# MODULO2_2.net
KiCad netlist of a schematic drawn in EAGLE
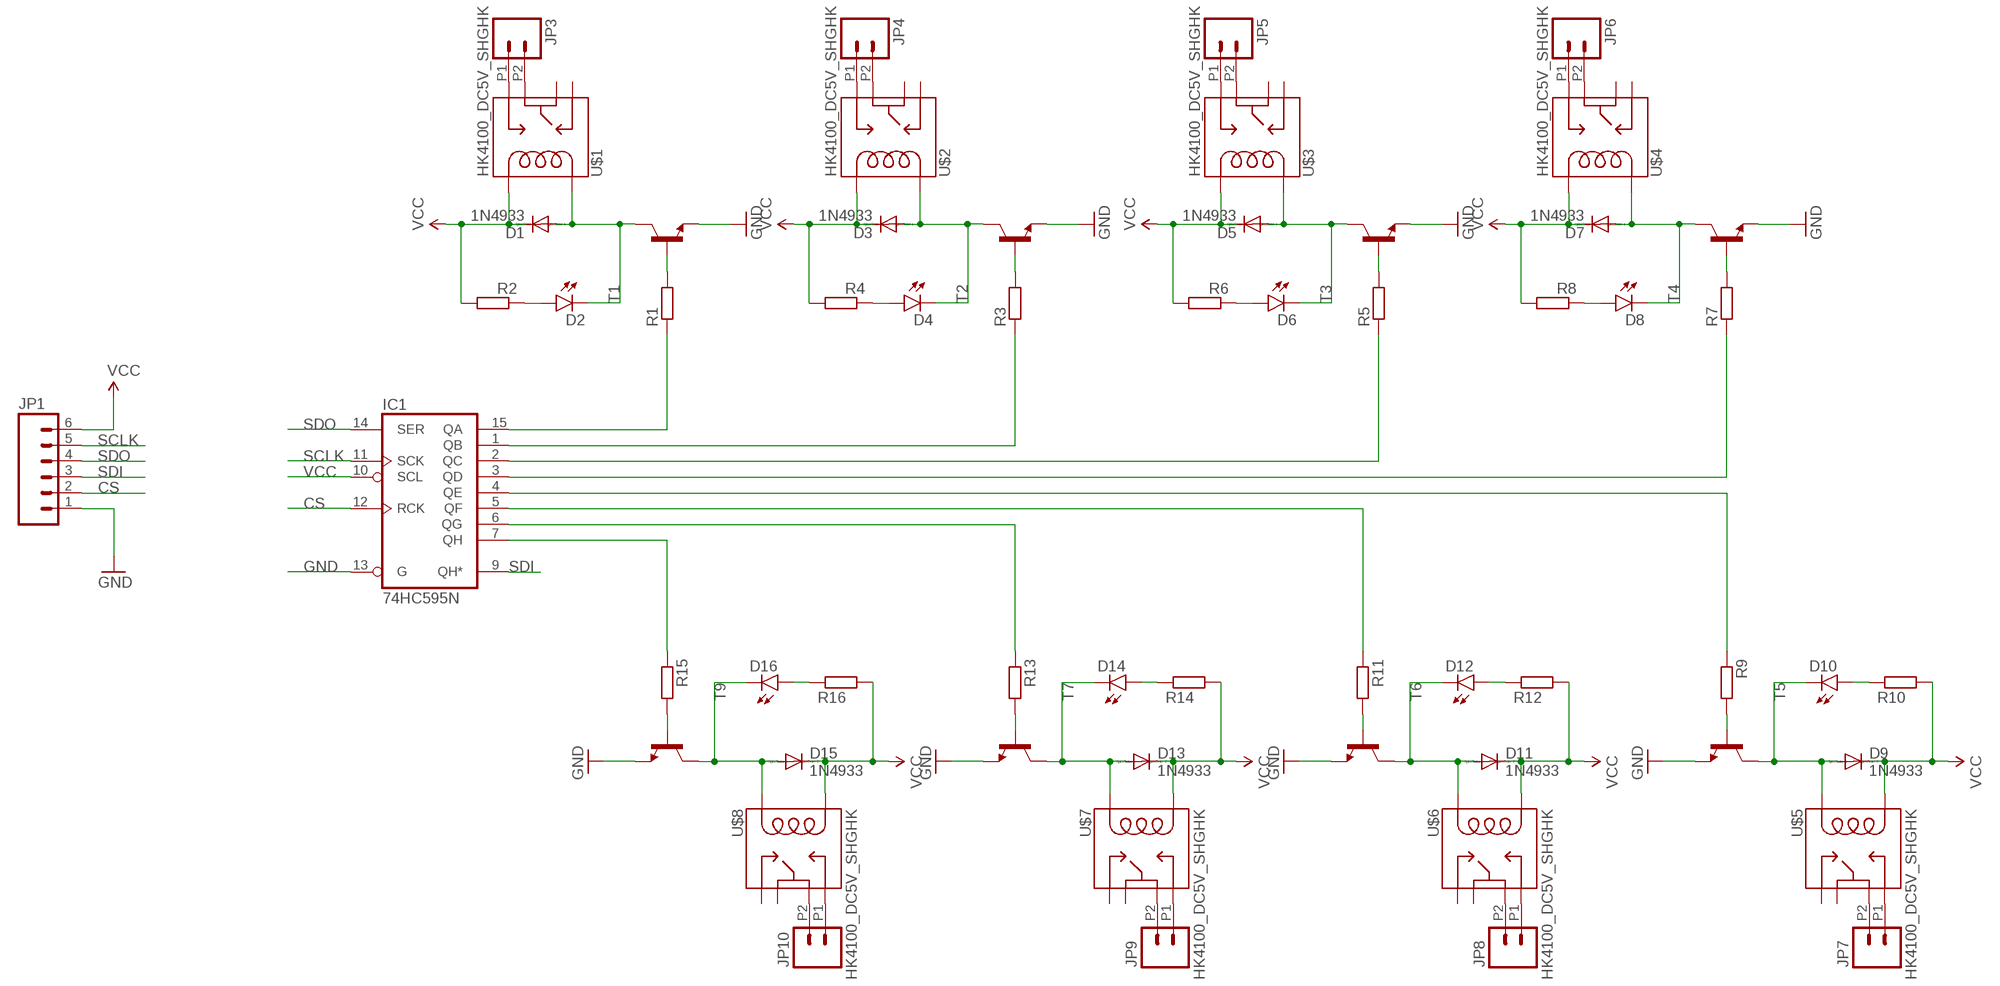
[diagram p0: schematic, sheet 1]

(export (version "E")
  (design (tool "Eeschema 10.0.6"))
  (components
    (comp (ref "D1")
      (value "1N4933")
      (footprint "eagle-import:DO41-10")
      (libsource (lib "eagle-import") (part "1N4933"))
    )
    (comp (ref "D2")
      (value "LED5MM")
      (footprint "eagle-import:LED5MM")
      (libsource (lib "eagle-import") (part "LED5MM"))
    )
    (comp (ref "D3")
      (value "1N4933")
      (footprint "eagle-import:DO41-10")
      (libsource (lib "eagle-import") (part "1N4933"))
    )
    (comp (ref "D4")
      (value "LED5MM")
      (footprint "eagle-import:LED5MM")
      (libsource (lib "eagle-import") (part "LED5MM"))
    )
    (comp (ref "D5")
      (value "1N4933")
      (footprint "eagle-import:DO41-10")
      (libsource (lib "eagle-import") (part "1N4933"))
    )
    (comp (ref "D6")
      (value "LED5MM")
      (footprint "eagle-import:LED5MM")
      (libsource (lib "eagle-import") (part "LED5MM"))
    )
    (comp (ref "D7")
      (value "1N4933")
      (footprint "eagle-import:DO41-10")
      (libsource (lib "eagle-import") (part "1N4933"))
    )
    (comp (ref "D8")
      (value "LED5MM")
      (footprint "eagle-import:LED5MM")
      (libsource (lib "eagle-import") (part "LED5MM"))
    )
    (comp (ref "D9")
      (value "1N4933")
      (footprint "eagle-import:DO41-10")
      (libsource (lib "eagle-import") (part "1N4933"))
    )
    (comp (ref "D10")
      (value "LED5MM")
      (footprint "eagle-import:LED5MM")
      (libsource (lib "eagle-import") (part "LED5MM"))
    )
    (comp (ref "D11")
      (value "1N4933")
      (footprint "eagle-import:DO41-10")
      (libsource (lib "eagle-import") (part "1N4933"))
    )
    (comp (ref "D12")
      (value "LED5MM")
      (footprint "eagle-import:LED5MM")
      (libsource (lib "eagle-import") (part "LED5MM"))
    )
    (comp (ref "D13")
      (value "1N4933")
      (footprint "eagle-import:DO41-10")
      (libsource (lib "eagle-import") (part "1N4933"))
    )
    (comp (ref "D14")
      (value "LED5MM")
      (footprint "eagle-import:LED5MM")
      (libsource (lib "eagle-import") (part "LED5MM"))
    )
    (comp (ref "D15")
      (value "1N4933")
      (footprint "eagle-import:DO41-10")
      (libsource (lib "eagle-import") (part "1N4933"))
    )
    (comp (ref "D16")
      (value "LED5MM")
      (footprint "eagle-import:LED5MM")
      (libsource (lib "eagle-import") (part "LED5MM"))
    )
    (comp (ref "IC1")
      (value "74HC595N")
      (footprint "eagle-import:DIL16")
      (libsource (lib "eagle-import") (part "74595NHC"))
    )
    (comp (ref "JP1")
      (value "M06LOCK")
      (footprint "eagle-import:1X06_LOCK")
      (libsource (lib "eagle-import") (part "M06LOCK"))
    )
    (comp (ref "JP3")
      (value "M022.54MM_SCREWTERM")
      (footprint "eagle-import:1X02_2.54_SCREWTERM")
      (libsource (lib "eagle-import") (part "M022.54MM_SCREWTERM"))
    )
    (comp (ref "JP4")
      (value "M022.54MM_SCREWTERM")
      (footprint "eagle-import:1X02_2.54_SCREWTERM")
      (libsource (lib "eagle-import") (part "M022.54MM_SCREWTERM"))
    )
    (comp (ref "JP5")
      (value "M022.54MM_SCREWTERM")
      (footprint "eagle-import:1X02_2.54_SCREWTERM")
      (libsource (lib "eagle-import") (part "M022.54MM_SCREWTERM"))
    )
    (comp (ref "JP6")
      (value "M022.54MM_SCREWTERM")
      (footprint "eagle-import:1X02_2.54_SCREWTERM")
      (libsource (lib "eagle-import") (part "M022.54MM_SCREWTERM"))
    )
    (comp (ref "JP7")
      (value "M022.54MM_SCREWTERM")
      (footprint "eagle-import:1X02_2.54_SCREWTERM")
      (libsource (lib "eagle-import") (part "M022.54MM_SCREWTERM"))
    )
    (comp (ref "JP8")
      (value "M022.54MM_SCREWTERM")
      (footprint "eagle-import:1X02_2.54_SCREWTERM")
      (libsource (lib "eagle-import") (part "M022.54MM_SCREWTERM"))
    )
    (comp (ref "JP9")
      (value "M022.54MM_SCREWTERM")
      (footprint "eagle-import:1X02_2.54_SCREWTERM")
      (libsource (lib "eagle-import") (part "M022.54MM_SCREWTERM"))
    )
    (comp (ref "JP10")
      (value "M022.54MM_SCREWTERM")
      (footprint "eagle-import:1X02_2.54_SCREWTERM")
      (libsource (lib "eagle-import") (part "M022.54MM_SCREWTERM"))
    )
    (comp (ref "R1")
      (value "R-EU_R0805")
      (footprint "eagle-import:R0805")
      (libsource (lib "eagle-import") (part "R-EU_R0805"))
    )
    (comp (ref "R2")
      (value "R-EU_R0805")
      (footprint "eagle-import:R0805")
      (libsource (lib "eagle-import") (part "R-EU_R0805"))
    )
    (comp (ref "R3")
      (value "R-EU_R0805")
      (footprint "eagle-import:R0805")
      (libsource (lib "eagle-import") (part "R-EU_R0805"))
    )
    (comp (ref "R4")
      (value "R-EU_R0805")
      (footprint "eagle-import:R0805")
      (libsource (lib "eagle-import") (part "R-EU_R0805"))
    )
    (comp (ref "R5")
      (value "R-EU_R0805")
      (footprint "eagle-import:R0805")
      (libsource (lib "eagle-import") (part "R-EU_R0805"))
    )
    (comp (ref "R6")
      (value "R-EU_R0805")
      (footprint "eagle-import:R0805")
      (libsource (lib "eagle-import") (part "R-EU_R0805"))
    )
    (comp (ref "R7")
      (value "R-EU_R0805")
      (footprint "eagle-import:R0805")
      (libsource (lib "eagle-import") (part "R-EU_R0805"))
    )
    (comp (ref "R8")
      (value "R-EU_R0805")
      (footprint "eagle-import:R0805")
      (libsource (lib "eagle-import") (part "R-EU_R0805"))
    )
    (comp (ref "R9")
      (value "R-EU_R0805")
      (footprint "eagle-import:R0805")
      (libsource (lib "eagle-import") (part "R-EU_R0805"))
    )
    (comp (ref "R10")
      (value "R-EU_R0805")
      (footprint "eagle-import:R0805")
      (libsource (lib "eagle-import") (part "R-EU_R0805"))
    )
    (comp (ref "R11")
      (value "R-EU_R0805")
      (footprint "eagle-import:R0805")
      (libsource (lib "eagle-import") (part "R-EU_R0805"))
    )
    (comp (ref "R12")
      (value "R-EU_R0805")
      (footprint "eagle-import:R0805")
      (libsource (lib "eagle-import") (part "R-EU_R0805"))
    )
    (comp (ref "R13")
      (value "R-EU_R0805")
      (footprint "eagle-import:R0805")
      (libsource (lib "eagle-import") (part "R-EU_R0805"))
    )
    (comp (ref "R14")
      (value "R-EU_R0805")
      (footprint "eagle-import:R0805")
      (libsource (lib "eagle-import") (part "R-EU_R0805"))
    )
    (comp (ref "R15")
      (value "R-EU_R0805")
      (footprint "eagle-import:R0805")
      (libsource (lib "eagle-import") (part "R-EU_R0805"))
    )
    (comp (ref "R16")
      (value "R-EU_R0805")
      (footprint "eagle-import:R0805")
      (libsource (lib "eagle-import") (part "R-EU_R0805"))
    )
    (comp (ref "T1")
      (value "-NPN-TO92-EBC")
      (footprint "eagle-import:TO92-EBC")
      (libsource (lib "eagle-import") (part "-NPN-TO92-EBC"))
    )
    (comp (ref "T2")
      (value "-NPN-TO92-EBC")
      (footprint "eagle-import:TO92-EBC")
      (libsource (lib "eagle-import") (part "-NPN-TO92-EBC"))
    )
    (comp (ref "T3")
      (value "-NPN-TO92-EBC")
      (footprint "eagle-import:TO92-EBC")
      (libsource (lib "eagle-import") (part "-NPN-TO92-EBC"))
    )
    (comp (ref "T4")
      (value "-NPN-TO92-EBC")
      (footprint "eagle-import:TO92-EBC")
      (libsource (lib "eagle-import") (part "-NPN-TO92-EBC"))
    )
    (comp (ref "T5")
      (value "-NPN-TO92-EBC")
      (footprint "eagle-import:TO92-EBC")
      (libsource (lib "eagle-import") (part "-NPN-TO92-EBC"))
    )
    (comp (ref "T6")
      (value "-NPN-TO92-EBC")
      (footprint "eagle-import:TO92-EBC")
      (libsource (lib "eagle-import") (part "-NPN-TO92-EBC"))
    )
    (comp (ref "T7")
      (value "-NPN-TO92-EBC")
      (footprint "eagle-import:TO92-EBC")
      (libsource (lib "eagle-import") (part "-NPN-TO92-EBC"))
    )
    (comp (ref "T9")
      (value "-NPN-TO92-EBC")
      (footprint "eagle-import:TO92-EBC")
      (libsource (lib "eagle-import") (part "-NPN-TO92-EBC"))
    )
    (comp (ref "U$1")
      (value "HK4100_DC5V_SHGHK")
      (footprint "eagle-import:HK4100")
      (libsource (lib "eagle-import") (part "HK4100_DC5V_SHGHK"))
    )
    (comp (ref "U$2")
      (value "HK4100_DC5V_SHGHK")
      (footprint "eagle-import:HK4100")
      (libsource (lib "eagle-import") (part "HK4100_DC5V_SHGHK"))
    )
    (comp (ref "U$3")
      (value "HK4100_DC5V_SHGHK")
      (footprint "eagle-import:HK4100")
      (libsource (lib "eagle-import") (part "HK4100_DC5V_SHGHK"))
    )
    (comp (ref "U$4")
      (value "HK4100_DC5V_SHGHK")
      (footprint "eagle-import:HK4100")
      (libsource (lib "eagle-import") (part "HK4100_DC5V_SHGHK"))
    )
    (comp (ref "U$5")
      (value "HK4100_DC5V_SHGHK")
      (footprint "eagle-import:HK4100")
      (libsource (lib "eagle-import") (part "HK4100_DC5V_SHGHK"))
    )
    (comp (ref "U$6")
      (value "HK4100_DC5V_SHGHK")
      (footprint "eagle-import:HK4100")
      (libsource (lib "eagle-import") (part "HK4100_DC5V_SHGHK"))
    )
    (comp (ref "U$7")
      (value "HK4100_DC5V_SHGHK")
      (footprint "eagle-import:HK4100")
      (libsource (lib "eagle-import") (part "HK4100_DC5V_SHGHK"))
    )
    (comp (ref "U$8")
      (value "HK4100_DC5V_SHGHK")
      (footprint "eagle-import:HK4100")
      (libsource (lib "eagle-import") (part "HK4100_DC5V_SHGHK"))
    )
  )
  (nets
    (net (code "1") (name "/CS") (class "Default")
      (node (ref "IC1") (pin "12") (pinfunction "RCK_12") (pintype "input"))
      (node (ref "JP1") (pin "2") (pinfunction "2_2") (pintype "passive"))
    )
    (net (code "2") (name "/SCLK") (class "Default")
      (node (ref "IC1") (pin "11") (pinfunction "SCK_11") (pintype "input"))
      (node (ref "JP1") (pin "5") (pinfunction "5_5") (pintype "passive"))
    )
    (net (code "3") (name "/SDI") (class "Default")
      (node (ref "IC1") (pin "9") (pinfunction "QH*_9") (pintype "tri_state"))
      (node (ref "JP1") (pin "3") (pinfunction "3_3") (pintype "passive"))
    )
    (net (code "4") (name "/SDO") (class "Default")
      (node (ref "IC1") (pin "14") (pinfunction "SER_14") (pintype "input"))
      (node (ref "JP1") (pin "4") (pinfunction "4_4") (pintype "passive"))
    )
    (net (code "5") (name "GND") (class "Default")
      (node (ref "IC1") (pin "13") (pinfunction "G_13") (pintype "input"))
      (node (ref "JP1") (pin "1") (pinfunction "1_1") (pintype "passive"))
      (node (ref "T1") (pin "E") (pinfunction "E_E") (pintype "passive"))
      (node (ref "T2") (pin "E") (pinfunction "E_E") (pintype "passive"))
      (node (ref "T3") (pin "E") (pinfunction "E_E") (pintype "passive"))
      (node (ref "T4") (pin "E") (pinfunction "E_E") (pintype "passive"))
      (node (ref "T5") (pin "E") (pinfunction "E_E") (pintype "passive"))
      (node (ref "T6") (pin "E") (pinfunction "E_E") (pintype "passive"))
      (node (ref "T7") (pin "E") (pinfunction "E_E") (pintype "passive"))
      (node (ref "T9") (pin "E") (pinfunction "E_E") (pintype "passive"))
    )
    (net (code "6") (name "Net-(D2-C)") (class "Default")
      (node (ref "D1") (pin "A") (pinfunction "A_A") (pintype "passive"))
      (node (ref "D2") (pin "K") (pinfunction "C_K") (pintype "passive"))
      (node (ref "T1") (pin "C") (pinfunction "C_C") (pintype "passive"))
      (node (ref "U$1") (pin "6") (pinfunction "2_6") (pintype "bidirectional"))
    )
    (net (code "7") (name "Net-(D2-PadA)") (class "Default")
      (node (ref "D2") (pin "A") (pinfunction "A_A") (pintype "passive"))
      (node (ref "R2") (pin "1") (pinfunction "1_1") (pintype "passive"))
    )
    (net (code "8") (name "Net-(D4-C)") (class "Default")
      (node (ref "D3") (pin "A") (pinfunction "A_A") (pintype "passive"))
      (node (ref "D4") (pin "K") (pinfunction "C_K") (pintype "passive"))
      (node (ref "T2") (pin "C") (pinfunction "C_C") (pintype "passive"))
      (node (ref "U$2") (pin "6") (pinfunction "2_6") (pintype "bidirectional"))
    )
    (net (code "9") (name "Net-(D4-PadA)") (class "Default")
      (node (ref "D4") (pin "A") (pinfunction "A_A") (pintype "passive"))
      (node (ref "R4") (pin "1") (pinfunction "1_1") (pintype "passive"))
    )
    (net (code "10") (name "Net-(D6-C)") (class "Default")
      (node (ref "D5") (pin "A") (pinfunction "A_A") (pintype "passive"))
      (node (ref "D6") (pin "K") (pinfunction "C_K") (pintype "passive"))
      (node (ref "T3") (pin "C") (pinfunction "C_C") (pintype "passive"))
      (node (ref "U$3") (pin "6") (pinfunction "2_6") (pintype "bidirectional"))
    )
    (net (code "11") (name "Net-(D6-PadA)") (class "Default")
      (node (ref "D6") (pin "A") (pinfunction "A_A") (pintype "passive"))
      (node (ref "R6") (pin "1") (pinfunction "1_1") (pintype "passive"))
    )
    (net (code "12") (name "Net-(D8-C)") (class "Default")
      (node (ref "D7") (pin "A") (pinfunction "A_A") (pintype "passive"))
      (node (ref "D8") (pin "K") (pinfunction "C_K") (pintype "passive"))
      (node (ref "T4") (pin "C") (pinfunction "C_C") (pintype "passive"))
      (node (ref "U$4") (pin "6") (pinfunction "2_6") (pintype "bidirectional"))
    )
    (net (code "13") (name "Net-(D8-PadA)") (class "Default")
      (node (ref "D8") (pin "A") (pinfunction "A_A") (pintype "passive"))
      (node (ref "R8") (pin "1") (pinfunction "1_1") (pintype "passive"))
    )
    (net (code "14") (name "Net-(D10-C)") (class "Default")
      (node (ref "D10") (pin "K") (pinfunction "C_K") (pintype "passive"))
      (node (ref "D9") (pin "A") (pinfunction "A_A") (pintype "passive"))
      (node (ref "T5") (pin "C") (pinfunction "C_C") (pintype "passive"))
      (node (ref "U$5") (pin "6") (pinfunction "2_6") (pintype "bidirectional"))
    )
    (net (code "15") (name "Net-(D10-PadA)") (class "Default")
      (node (ref "D10") (pin "A") (pinfunction "A_A") (pintype "passive"))
      (node (ref "R10") (pin "1") (pinfunction "1_1") (pintype "passive"))
    )
    (net (code "16") (name "Net-(D12-C)") (class "Default")
      (node (ref "D11") (pin "A") (pinfunction "A_A") (pintype "passive"))
      (node (ref "D12") (pin "K") (pinfunction "C_K") (pintype "passive"))
      (node (ref "T6") (pin "C") (pinfunction "C_C") (pintype "passive"))
      (node (ref "U$6") (pin "6") (pinfunction "2_6") (pintype "bidirectional"))
    )
    (net (code "17") (name "Net-(D12-PadA)") (class "Default")
      (node (ref "D12") (pin "A") (pinfunction "A_A") (pintype "passive"))
      (node (ref "R12") (pin "1") (pinfunction "1_1") (pintype "passive"))
    )
    (net (code "18") (name "Net-(D14-C)") (class "Default")
      (node (ref "D13") (pin "A") (pinfunction "A_A") (pintype "passive"))
      (node (ref "D14") (pin "K") (pinfunction "C_K") (pintype "passive"))
      (node (ref "T7") (pin "C") (pinfunction "C_C") (pintype "passive"))
      (node (ref "U$7") (pin "6") (pinfunction "2_6") (pintype "bidirectional"))
    )
    (net (code "19") (name "Net-(D14-PadA)") (class "Default")
      (node (ref "D14") (pin "A") (pinfunction "A_A") (pintype "passive"))
      (node (ref "R14") (pin "1") (pinfunction "1_1") (pintype "passive"))
    )
    (net (code "20") (name "Net-(D16-C)") (class "Default")
      (node (ref "D15") (pin "A") (pinfunction "A_A") (pintype "passive"))
      (node (ref "D16") (pin "K") (pinfunction "C_K") (pintype "passive"))
      (node (ref "T9") (pin "C") (pinfunction "C_C") (pintype "passive"))
      (node (ref "U$8") (pin "6") (pinfunction "2_6") (pintype "bidirectional"))
    )
    (net (code "21") (name "Net-(D16-PadA)") (class "Default")
      (node (ref "D16") (pin "A") (pinfunction "A_A") (pintype "passive"))
      (node (ref "R16") (pin "1") (pinfunction "1_1") (pintype "passive"))
    )
    (net (code "22") (name "Net-(IC1A-QA)") (class "Default")
      (node (ref "IC1") (pin "15") (pinfunction "QA_15") (pintype "tri_state"))
      (node (ref "R1") (pin "1") (pinfunction "1_1") (pintype "passive"))
    )
    (net (code "23") (name "Net-(IC1A-QB)") (class "Default")
      (node (ref "IC1") (pin "1") (pinfunction "QB_1") (pintype "tri_state"))
      (node (ref "R3") (pin "1") (pinfunction "1_1") (pintype "passive"))
    )
    (net (code "24") (name "Net-(IC1A-QC)") (class "Default")
      (node (ref "IC1") (pin "2") (pinfunction "QC_2") (pintype "tri_state"))
      (node (ref "R5") (pin "1") (pinfunction "1_1") (pintype "passive"))
    )
    (net (code "25") (name "Net-(IC1A-QD)") (class "Default")
      (node (ref "IC1") (pin "3") (pinfunction "QD_3") (pintype "tri_state"))
      (node (ref "R7") (pin "1") (pinfunction "1_1") (pintype "passive"))
    )
    (net (code "26") (name "Net-(IC1A-QE)") (class "Default")
      (node (ref "IC1") (pin "4") (pinfunction "QE_4") (pintype "tri_state"))
      (node (ref "R9") (pin "1") (pinfunction "1_1") (pintype "passive"))
    )
    (net (code "27") (name "Net-(IC1A-QF)") (class "Default")
      (node (ref "IC1") (pin "5") (pinfunction "QF_5") (pintype "tri_state"))
      (node (ref "R11") (pin "1") (pinfunction "1_1") (pintype "passive"))
    )
    (net (code "28") (name "Net-(IC1A-QG)") (class "Default")
      (node (ref "IC1") (pin "6") (pinfunction "QG_6") (pintype "tri_state"))
      (node (ref "R13") (pin "1") (pinfunction "1_1") (pintype "passive"))
    )
    (net (code "29") (name "Net-(IC1A-QH)") (class "Default")
      (node (ref "IC1") (pin "7") (pinfunction "QH_7") (pintype "tri_state"))
      (node (ref "R15") (pin "1") (pinfunction "1_1") (pintype "passive"))
    )
    (net (code "30") (name "Net-(JP3-1)") (class "Default")
      (node (ref "JP3") (pin "P1") (pinfunction "1_P1") (pintype "passive"))
      (node (ref "U$1") (pin "8") (pinfunction "10_8") (pintype "bidirectional"))
    )
    (net (code "31") (name "Net-(JP3-2)") (class "Default")
      (node (ref "JP3") (pin "P2") (pinfunction "2_P2") (pintype "passive"))
      (node (ref "U$1") (pin "14") (pinfunction "6_14") (pintype "bidirectional"))
    )
    (net (code "32") (name "Net-(JP4-1)") (class "Default")
      (node (ref "JP4") (pin "P1") (pinfunction "1_P1") (pintype "passive"))
      (node (ref "U$2") (pin "8") (pinfunction "10_8") (pintype "bidirectional"))
    )
    (net (code "33") (name "Net-(JP4-2)") (class "Default")
      (node (ref "JP4") (pin "P2") (pinfunction "2_P2") (pintype "passive"))
      (node (ref "U$2") (pin "14") (pinfunction "6_14") (pintype "bidirectional"))
    )
    (net (code "34") (name "Net-(JP5-1)") (class "Default")
      (node (ref "JP5") (pin "P1") (pinfunction "1_P1") (pintype "passive"))
      (node (ref "U$3") (pin "8") (pinfunction "10_8") (pintype "bidirectional"))
    )
    (net (code "35") (name "Net-(JP5-2)") (class "Default")
      (node (ref "JP5") (pin "P2") (pinfunction "2_P2") (pintype "passive"))
      (node (ref "U$3") (pin "14") (pinfunction "6_14") (pintype "bidirectional"))
    )
    (net (code "36") (name "Net-(JP6-1)") (class "Default")
      (node (ref "JP6") (pin "P1") (pinfunction "1_P1") (pintype "passive"))
      (node (ref "U$4") (pin "8") (pinfunction "10_8") (pintype "bidirectional"))
    )
    (net (code "37") (name "Net-(JP6-2)") (class "Default")
      (node (ref "JP6") (pin "P2") (pinfunction "2_P2") (pintype "passive"))
      (node (ref "U$4") (pin "14") (pinfunction "6_14") (pintype "bidirectional"))
    )
    (net (code "38") (name "Net-(JP7-1)") (class "Default")
      (node (ref "JP7") (pin "P1") (pinfunction "1_P1") (pintype "passive"))
      (node (ref "U$5") (pin "8") (pinfunction "10_8") (pintype "bidirectional"))
    )
    (net (code "39") (name "Net-(JP7-2)") (class "Default")
      (node (ref "JP7") (pin "P2") (pinfunction "2_P2") (pintype "passive"))
      (node (ref "U$5") (pin "14") (pinfunction "6_14") (pintype "bidirectional"))
    )
    (net (code "40") (name "Net-(JP8-1)") (class "Default")
      (node (ref "JP8") (pin "P1") (pinfunction "1_P1") (pintype "passive"))
      (node (ref "U$6") (pin "8") (pinfunction "10_8") (pintype "bidirectional"))
    )
    (net (code "41") (name "Net-(JP8-2)") (class "Default")
      (node (ref "JP8") (pin "P2") (pinfunction "2_P2") (pintype "passive"))
      (node (ref "U$6") (pin "14") (pinfunction "6_14") (pintype "bidirectional"))
    )
    (net (code "42") (name "Net-(JP9-1)") (class "Default")
      (node (ref "JP9") (pin "P1") (pinfunction "1_P1") (pintype "passive"))
      (node (ref "U$7") (pin "8") (pinfunction "10_8") (pintype "bidirectional"))
    )
    (net (code "43") (name "Net-(JP9-2)") (class "Default")
      (node (ref "JP9") (pin "P2") (pinfunction "2_P2") (pintype "passive"))
      (node (ref "U$7") (pin "14") (pinfunction "6_14") (pintype "bidirectional"))
    )
    (net (code "44") (name "Net-(JP10-1)") (class "Default")
      (node (ref "JP10") (pin "P1") (pinfunction "1_P1") (pintype "passive"))
      (node (ref "U$8") (pin "8") (pinfunction "10_8") (pintype "bidirectional"))
    )
    (net (code "45") (name "Net-(JP10-2)") (class "Default")
      (node (ref "JP10") (pin "P2") (pinfunction "2_P2") (pintype "passive"))
      (node (ref "U$8") (pin "14") (pinfunction "6_14") (pintype "bidirectional"))
    )
    (net (code "46") (name "Net-(R1-Pad2)") (class "Default")
      (node (ref "R1") (pin "2") (pinfunction "2_2") (pintype "passive"))
      (node (ref "T1") (pin "B") (pinfunction "B_B") (pintype "passive"))
    )
    (net (code "47") (name "Net-(R3-Pad2)") (class "Default")
      (node (ref "R3") (pin "2") (pinfunction "2_2") (pintype "passive"))
      (node (ref "T2") (pin "B") (pinfunction "B_B") (pintype "passive"))
    )
    (net (code "48") (name "Net-(R5-Pad2)") (class "Default")
      (node (ref "R5") (pin "2") (pinfunction "2_2") (pintype "passive"))
      (node (ref "T3") (pin "B") (pinfunction "B_B") (pintype "passive"))
    )
    (net (code "49") (name "Net-(R7-Pad2)") (class "Default")
      (node (ref "R7") (pin "2") (pinfunction "2_2") (pintype "passive"))
      (node (ref "T4") (pin "B") (pinfunction "B_B") (pintype "passive"))
    )
    (net (code "50") (name "Net-(R9-Pad2)") (class "Default")
      (node (ref "R9") (pin "2") (pinfunction "2_2") (pintype "passive"))
      (node (ref "T5") (pin "B") (pinfunction "B_B") (pintype "passive"))
    )
    (net (code "51") (name "Net-(R11-Pad2)") (class "Default")
      (node (ref "R11") (pin "2") (pinfunction "2_2") (pintype "passive"))
      (node (ref "T6") (pin "B") (pinfunction "B_B") (pintype "passive"))
    )
    (net (code "52") (name "Net-(R13-Pad2)") (class "Default")
      (node (ref "R13") (pin "2") (pinfunction "2_2") (pintype "passive"))
      (node (ref "T7") (pin "B") (pinfunction "B_B") (pintype "passive"))
    )
    (net (code "53") (name "Net-(R15-Pad2)") (class "Default")
      (node (ref "R15") (pin "2") (pinfunction "2_2") (pintype "passive"))
      (node (ref "T9") (pin "B") (pinfunction "B_B") (pintype "passive"))
    )
    (net (code "54") (name "VCC") (class "Default")
      (node (ref "D1") (pin "C") (pinfunction "C_C") (pintype "passive"))
      (node (ref "D11") (pin "C") (pinfunction "C_C") (pintype "passive"))
      (node (ref "D13") (pin "C") (pinfunction "C_C") (pintype "passive"))
      (node (ref "D15") (pin "C") (pinfunction "C_C") (pintype "passive"))
      (node (ref "D3") (pin "C") (pinfunction "C_C") (pintype "passive"))
      (node (ref "D5") (pin "C") (pinfunction "C_C") (pintype "passive"))
      (node (ref "D7") (pin "C") (pinfunction "C_C") (pintype "passive"))
      (node (ref "D9") (pin "C") (pinfunction "C_C") (pintype "passive"))
      (node (ref "IC1") (pin "10") (pinfunction "SCL_10") (pintype "input"))
      (node (ref "JP1") (pin "6") (pinfunction "6_6") (pintype "passive"))
      (node (ref "R10") (pin "2") (pinfunction "2_2") (pintype "passive"))
      (node (ref "R12") (pin "2") (pinfunction "2_2") (pintype "passive"))
      (node (ref "R14") (pin "2") (pinfunction "2_2") (pintype "passive"))
      (node (ref "R16") (pin "2") (pinfunction "2_2") (pintype "passive"))
      (node (ref "R2") (pin "2") (pinfunction "2_2") (pintype "passive"))
      (node (ref "R4") (pin "2") (pinfunction "2_2") (pintype "passive"))
      (node (ref "R6") (pin "2") (pinfunction "2_2") (pintype "passive"))
      (node (ref "R8") (pin "2") (pinfunction "2_2") (pintype "passive"))
      (node (ref "U$1") (pin "9") (pinfunction "9_9") (pintype "bidirectional"))
      (node (ref "U$2") (pin "9") (pinfunction "9_9") (pintype "bidirectional"))
      (node (ref "U$3") (pin "9") (pinfunction "9_9") (pintype "bidirectional"))
      (node (ref "U$4") (pin "9") (pinfunction "9_9") (pintype "bidirectional"))
      (node (ref "U$5") (pin "9") (pinfunction "9_9") (pintype "bidirectional"))
      (node (ref "U$6") (pin "9") (pinfunction "9_9") (pintype "bidirectional"))
      (node (ref "U$7") (pin "9") (pinfunction "9_9") (pintype "bidirectional"))
      (node (ref "U$8") (pin "9") (pinfunction "9_9") (pintype "bidirectional"))
    )
    (net (code "55") (name "unconnected-(U$1-1-Pad7)") (class "Default")
      (node (ref "U$1") (pin "7") (pinfunction "1_7") (pintype "bidirectional"))
    )
    (net (code "56") (name "unconnected-(U$1-5-Pad1)") (class "Default")
      (node (ref "U$1") (pin "1") (pinfunction "5_1") (pintype "bidirectional"))
    )
    (net (code "57") (name "unconnected-(U$2-1-Pad7)") (class "Default")
      (node (ref "U$2") (pin "7") (pinfunction "1_7") (pintype "bidirectional"))
    )
    (net (code "58") (name "unconnected-(U$2-5-Pad1)") (class "Default")
      (node (ref "U$2") (pin "1") (pinfunction "5_1") (pintype "bidirectional"))
    )
    (net (code "59") (name "unconnected-(U$3-1-Pad7)") (class "Default")
      (node (ref "U$3") (pin "7") (pinfunction "1_7") (pintype "bidirectional"))
    )
    (net (code "60") (name "unconnected-(U$3-5-Pad1)") (class "Default")
      (node (ref "U$3") (pin "1") (pinfunction "5_1") (pintype "bidirectional"))
    )
    (net (code "61") (name "unconnected-(U$4-1-Pad7)") (class "Default")
      (node (ref "U$4") (pin "7") (pinfunction "1_7") (pintype "bidirectional"))
    )
    (net (code "62") (name "unconnected-(U$4-5-Pad1)") (class "Default")
      (node (ref "U$4") (pin "1") (pinfunction "5_1") (pintype "bidirectional"))
    )
    (net (code "63") (name "unconnected-(U$5-1-Pad7)") (class "Default")
      (node (ref "U$5") (pin "7") (pinfunction "1_7") (pintype "bidirectional"))
    )
    (net (code "64") (name "unconnected-(U$5-5-Pad1)") (class "Default")
      (node (ref "U$5") (pin "1") (pinfunction "5_1") (pintype "bidirectional"))
    )
    (net (code "65") (name "unconnected-(U$6-1-Pad7)") (class "Default")
      (node (ref "U$6") (pin "7") (pinfunction "1_7") (pintype "bidirectional"))
    )
    (net (code "66") (name "unconnected-(U$6-5-Pad1)") (class "Default")
      (node (ref "U$6") (pin "1") (pinfunction "5_1") (pintype "bidirectional"))
    )
    (net (code "67") (name "unconnected-(U$7-1-Pad7)") (class "Default")
      (node (ref "U$7") (pin "7") (pinfunction "1_7") (pintype "bidirectional"))
    )
    (net (code "68") (name "unconnected-(U$7-5-Pad1)") (class "Default")
      (node (ref "U$7") (pin "1") (pinfunction "5_1") (pintype "bidirectional"))
    )
    (net (code "69") (name "unconnected-(U$8-1-Pad7)") (class "Default")
      (node (ref "U$8") (pin "7") (pinfunction "1_7") (pintype "bidirectional"))
    )
    (net (code "70") (name "unconnected-(U$8-5-Pad1)") (class "Default")
      (node (ref "U$8") (pin "1") (pinfunction "5_1") (pintype "bidirectional"))
    )
  )
)
